# 3.net
KiCad netlist of a schematic drawn in Altium Designer
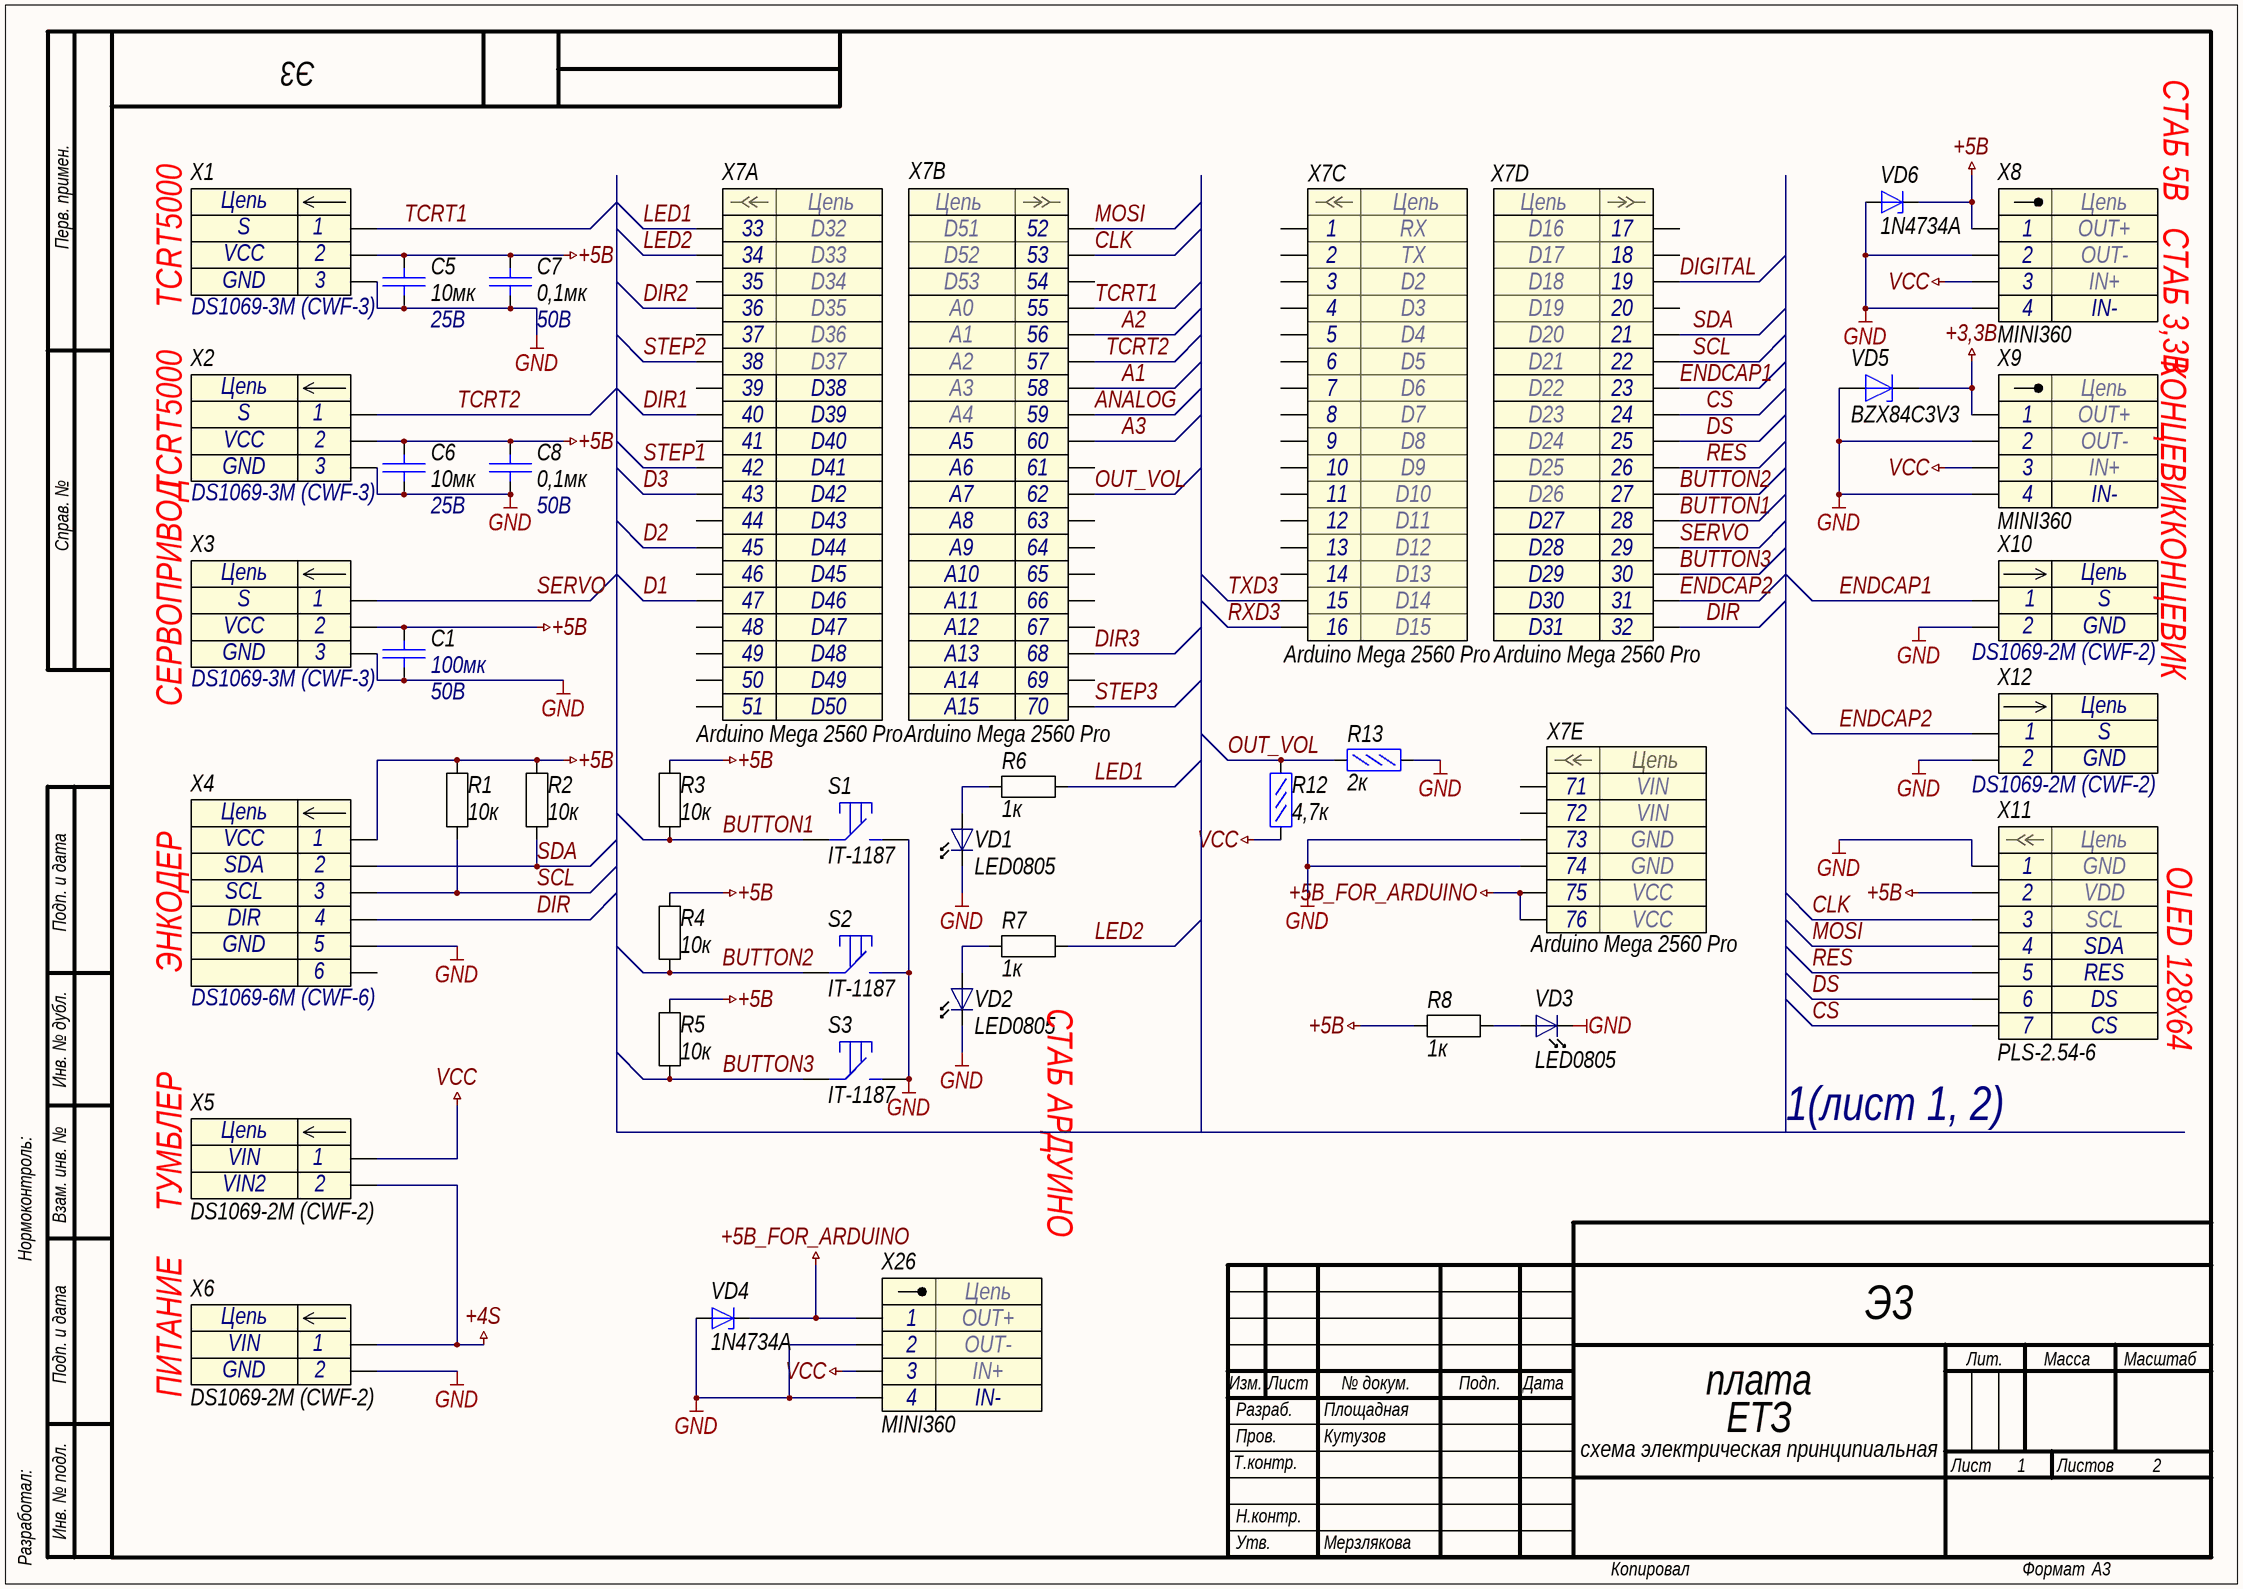
[diagram p0: Э3.SchDoc]

(export (version "E")
  (design (tool "Eeschema 10.0.6"))
  (components
    (comp (ref "C1")
      (value "100мк")
      (footprint "C1210")
      (description "Конденсатор кер. 100мк 50В")
      (fields (field (name "MANUFACTURER") "Yageo") (field (name "VOLTAGE") "50В"))
      (libsource (lib "capacitors") (part "CC0603JRNPO9BN220"))
    )
    (comp (ref "C5")
      (value "10мк")
      (footprint "C1206")
      (description "Конденсатор кер. 10мкФ 25В")
      (fields (field (name "MANUFACTURER") "Yageo") (field (name "VOLTAGE") "25В"))
      (libsource (lib "capacitors") (part "CC1206KKX7R8BB106"))
    )
    (comp (ref "C6")
      (value "10мк")
      (footprint "C1206")
      (description "Конденсатор кер. 10мкФ 25В")
      (fields (field (name "MANUFACTURER") "Yageo") (field (name "VOLTAGE") "25В"))
      (libsource (lib "capacitors") (part "CC1206KKX7R8BB106"))
    )
    (comp (ref "C7")
      (value "0,1мк")
      (footprint "C0603")
      (description "Конденсатор кер. 0,1мкФ 50В X7R")
      (fields (field (name "MANUFACTURER") "Murata") (field (name "VOLTAGE") "50В"))
      (libsource (lib "capacitors") (part "GRM188R71H104KA93D"))
    )
    (comp (ref "C8")
      (value "0,1мк")
      (footprint "C0603")
      (description "Конденсатор кер. 0,1мкФ 50В X7R")
      (fields (field (name "MANUFACTURER") "Murata") (field (name "VOLTAGE") "50В"))
      (libsource (lib "capacitors") (part "GRM188R71H104KA93D"))
    )
    (comp (ref "R1") (value "10к") (footprint "Resistor0805") (libsource (lib "") (part "RESISTOR_2")))
    (comp (ref "R2") (value "10к") (footprint "Resistor0805") (libsource (lib "") (part "RESISTOR_2")))
    (comp (ref "R3") (value "10к") (footprint "Resistor0805") (libsource (lib "") (part "RESISTOR_1")))
    (comp (ref "R4") (value "10к") (footprint "Resistor0805") (libsource (lib "") (part "RESISTOR_1")))
    (comp (ref "R5") (value "10к") (footprint "Resistor0805") (libsource (lib "") (part "RESISTOR_1")))
    (comp (ref "R6")
      (value "1к")
      (footprint "Resistor0805")
      (libsource (lib "LibraryPloshchadnaia") (part "RESISTOR"))
    )
    (comp (ref "R7")
      (value "1к")
      (footprint "Resistor0805")
      (libsource (lib "LibraryPloshchadnaia") (part "RESISTOR"))
    )
    (comp (ref "R8") (value "1к") (footprint "Resistor0805") (libsource (lib "") (part "RESISTOR_3")))
    (comp (ref "R12")
      (value "4,7к")
      (footprint "R0603")
      (description "Резистор 4,7кОм 0,063Вт 1%")
      (fields (field (name "MANUFACTURER") "YAGEO") (field (name "TOLERANCE") "1%"))
      (libsource (lib "resistors") (part "RC0603FR-074K7L"))
    )
    (comp (ref "R13")
      (value "2к")
      (footprint "R0603")
      (description "Резистор 2кОм 0,063Вт 1%")
      (fields (field (name "MANUFACTURER") "YAGEO") (field (name "TOLERANCE") "1%"))
      (libsource (lib "resistors") (part "RC0603FR-072KL"))
    )
    (comp (ref "S1")
      (value "IT-1187")
      (footprint "it-1187")
      (description "тактовая кнопка SMD")
      (libsource (lib "switches") (part "IT-1187"))
    )
    (comp (ref "S2")
      (value "IT-1187")
      (footprint "it-1187")
      (description "тактовая кнопка SMD")
      (libsource (lib "switches") (part "IT-1187"))
    )
    (comp (ref "S3")
      (value "IT-1187")
      (footprint "it-1187")
      (description "тактовая кнопка SMD")
      (libsource (lib "switches") (part "IT-1187"))
    )
    (comp (ref "VD1")
      (value "LED0805")
      (footprint "LED0805")
      (libsource (lib "LibraryPloshchadnaia") (part "LED0805"))
    )
    (comp (ref "VD2")
      (value "LED0805")
      (footprint "LED0805")
      (libsource (lib "LibraryPloshchadnaia") (part "LED0805"))
    )
    (comp (ref "VD3")
      (value "LED0805")
      (footprint "LED0805")
      (libsource (lib "LibraryPloshchadnaia") (part "LED0805"))
    )
    (comp (ref "VD4")
      (value "1N4734A")
      (footprint "DO-41")
      (description "Стабилитрон 5.6В, 5%, 1Вт, 1N4734A")
      (libsource (lib "diodes") (part "1N4734A"))
    )
    (comp (ref "VD5")
      (value "BZX84C3V3")
      (footprint "SOT23-3")
      (description "Стабилитрон 3,3В")
      (libsource (lib "diodes") (part "BZX84C3V3"))
    )
    (comp (ref "VD6")
      (value "1N4734A")
      (footprint "DO-41")
      (description "Стабилитрон 5.6В, 5%, 1Вт, 1N4734A")
      (libsource (lib "diodes") (part "1N4734A"))
    )
    (comp (ref "X1")
      (value "DS1069-3M (CWF-3)")
      (footprint "CWF-3")
      (description "Разъем - 3 конт. прямая вилка на плату")
      (fields (field (name "NAME") "DS1069-3M (CWF-3)"))
      (libsource (lib "headers") (part "CWF-3"))
    )
    (comp (ref "X2")
      (value "DS1069-3M (CWF-3)")
      (footprint "CWF-3")
      (description "Разъем - 3 конт. прямая вилка на плату")
      (fields (field (name "NAME") "DS1069-3M (CWF-3)"))
      (libsource (lib "headers") (part "CWF-3"))
    )
    (comp (ref "X3")
      (value "DS1069-3M (CWF-3)")
      (footprint "CWF-3")
      (description "Разъем - 3 конт. прямая вилка на плату")
      (fields (field (name "NAME") "DS1069-3M (CWF-3)"))
      (libsource (lib "headers") (part "CWF-3"))
    )
    (comp (ref "X4")
      (value "DS1069-6M (CWF-6)")
      (footprint "CWF-6")
      (description "Разъем - 6 конт. прямая вилка на плату")
      (fields (field (name "NAME") "DS1069-6M (CWF-6)"))
      (libsource (lib "headers") (part "CWF-6"))
    )
    (comp (ref "X5")
      (value "DS1069-2M (CWF-2)")
      (footprint "CWF-2")
      (description "Разъем - 2 конт. прямая вилка на плату")
      (libsource (lib "headers") (part "CWF-2"))
    )
    (comp (ref "X6")
      (value "DS1069-2M (CWF-2)")
      (footprint "CWF-2")
      (description "Разъем - 2 конт. прямая вилка на плату")
      (libsource (lib "headers") (part "CWF-2"))
    )
    (comp (ref "X7")
      (value "Arduino Mega 2560 Pro")
      (footprint "PBD38")
      (libsource (lib "LibraryPloshchadnaia") (part "Arduino Mega 2560 Pro"))
    )
    (comp (ref "X8")
      (value "MINI360")
      (footprint "mini360")
      (description "стаб 18 на 12 мм")
      (libsource (lib "LibraryPloshchadnaia") (part "mini360"))
    )
    (comp (ref "X9")
      (value "MINI360")
      (footprint "mini360")
      (description "стаб 18 на 12 мм")
      (libsource (lib "LibraryPloshchadnaia") (part "mini360"))
    )
    (comp (ref "X10")
      (value "DS1069-2M (CWF-2)")
      (footprint "CWF-2")
      (description "Разъем - 2 конт. прямая вилка на плату")
      (fields (field (name "NAME") "DS1069-2M (CWF-2)"))
      (libsource (lib "") (part "CWF-2_1"))
    )
    (comp (ref "X11")
      (value "PLS-2.54-6")
      (footprint "PBD8")
      (libsource (lib "LibraryPloshchadnaia") (part "PBD8"))
    )
    (comp (ref "X12")
      (value "DS1069-2M (CWF-2)")
      (footprint "CWF-2")
      (description "Разъем - 2 конт. прямая вилка на плату")
      (fields (field (name "NAME") "DS1069-2M (CWF-2)"))
      (libsource (lib "") (part "CWF-2_1"))
    )
    (comp (ref "X26")
      (value "MINI360")
      (footprint "mini360")
      (description "стаб 18 на 12 мм")
      (libsource (lib "LibraryPloshchadnaia") (part "mini360"))
    )
  )
  (nets
    (net (code "1") (name "+3,3В") (class "Default")
      (node (ref "VD5") (pin "3") (pinfunction "K_3") (pintype "passive"))
      (node (ref "X9") (pin "1") (pinfunction "1_1") (pintype "passive"))
    )
    (net (code "2") (name "+4S") (class "Default")
      (node (ref "X5") (pin "2") (pinfunction "2_2") (pintype "passive"))
      (node (ref "X6") (pin "1") (pinfunction "1_1") (pintype "passive"))
    )
    (net (code "3") (name "+5В") (class "Default")
      (node (ref "C1") (pin "2") (pinfunction "2_2") (pintype "passive"))
      (node (ref "C5") (pin "2") (pinfunction "2_2") (pintype "passive"))
      (node (ref "C6") (pin "2") (pinfunction "2_2") (pintype "passive"))
      (node (ref "C7") (pin "2") (pinfunction "2_2") (pintype "passive"))
      (node (ref "C8") (pin "2") (pinfunction "2_2") (pintype "passive"))
      (node (ref "R1") (pin "1") (pinfunction "1_1") (pintype "passive"))
      (node (ref "R2") (pin "1") (pinfunction "1_1") (pintype "passive"))
      (node (ref "R3") (pin "2") (pinfunction "2_2") (pintype "passive"))
      (node (ref "R4") (pin "2") (pinfunction "2_2") (pintype "passive"))
      (node (ref "R5") (pin "2") (pinfunction "2_2") (pintype "passive"))
      (node (ref "R8") (pin "1") (pinfunction "1_1") (pintype "passive"))
      (node (ref "VD6") (pin "2") (pinfunction "K_2") (pintype "passive"))
      (node (ref "X1") (pin "2") (pinfunction "2_2") (pintype "passive"))
      (node (ref "X11") (pin "2") (pinfunction "2_2") (pintype "passive"))
      (node (ref "X2") (pin "2") (pinfunction "2_2") (pintype "passive"))
      (node (ref "X3") (pin "2") (pinfunction "2_2") (pintype "passive"))
      (node (ref "X4") (pin "1") (pinfunction "1_1") (pintype "passive"))
      (node (ref "X8") (pin "1") (pinfunction "1_1") (pintype "passive"))
    )
    (net (code "4") (name "+5В_FOR_ARDUINO") (class "Default")
      (node (ref "VD4") (pin "2") (pinfunction "K_2") (pintype "passive"))
      (node (ref "X26") (pin "1") (pinfunction "1_1") (pintype "passive"))
      (node (ref "X7") (pin "75") (pinfunction "75_75") (pintype "passive"))
      (node (ref "X7") (pin "76") (pinfunction "76_76") (pintype "passive"))
    )
    (net (code "5") (name "/A1") (class "Default")
      (node (ref "X7") (pin "58") (pinfunction "58_58") (pintype "passive"))
    )
    (net (code "6") (name "/A2") (class "Default")
      (node (ref "X7") (pin "56") (pinfunction "56_56") (pintype "passive"))
    )
    (net (code "7") (name "/A3") (class "Default")
      (node (ref "X7") (pin "60") (pinfunction "60_60") (pintype "passive"))
    )
    (net (code "8") (name "/ANALOG") (class "Default")
      (node (ref "X7") (pin "59") (pinfunction "59_59") (pintype "passive"))
    )
    (net (code "9") (name "/BUTTON1") (class "Default")
      (node (ref "R3") (pin "1") (pinfunction "1_1") (pintype "passive"))
      (node (ref "S1") (pin "1") (pinfunction "1_1") (pintype "passive"))
      (node (ref "X7") (pin "28") (pinfunction "28_28") (pintype "passive"))
    )
    (net (code "10") (name "/BUTTON2") (class "Default")
      (node (ref "R4") (pin "1") (pinfunction "1_1") (pintype "passive"))
      (node (ref "S2") (pin "1") (pinfunction "1_1") (pintype "passive"))
      (node (ref "X7") (pin "27") (pinfunction "27_27") (pintype "passive"))
    )
    (net (code "11") (name "/BUTTON3") (class "Default")
      (node (ref "R5") (pin "1") (pinfunction "1_1") (pintype "passive"))
      (node (ref "S3") (pin "1") (pinfunction "1_1") (pintype "passive"))
      (node (ref "X7") (pin "30") (pinfunction "30_30") (pintype "passive"))
    )
    (net (code "12") (name "/CLK") (class "Default")
      (node (ref "X11") (pin "3") (pinfunction "3_3") (pintype "passive"))
      (node (ref "X7") (pin "53") (pinfunction "53_53") (pintype "passive"))
    )
    (net (code "13") (name "/CS") (class "Default")
      (node (ref "X11") (pin "7") (pinfunction "7_7") (pintype "passive"))
      (node (ref "X7") (pin "24") (pinfunction "24_24") (pintype "passive"))
    )
    (net (code "14") (name "/D1") (class "Default")
      (node (ref "X7") (pin "47") (pinfunction "47_47") (pintype "passive"))
    )
    (net (code "15") (name "/D2") (class "Default")
      (node (ref "X7") (pin "45") (pinfunction "45_45") (pintype "passive"))
    )
    (net (code "16") (name "/D3") (class "Default")
      (node (ref "X7") (pin "43") (pinfunction "43_43") (pintype "passive"))
    )
    (net (code "17") (name "/DIGITAL") (class "Default")
      (node (ref "X7") (pin "19") (pinfunction "19_19") (pintype "passive"))
    )
    (net (code "18") (name "/DIR") (class "Default")
      (node (ref "X4") (pin "4") (pinfunction "4_4") (pintype "passive"))
      (node (ref "X7") (pin "32") (pinfunction "32_32") (pintype "passive"))
    )
    (net (code "19") (name "/DIR1") (class "Default")
      (node (ref "X7") (pin "40") (pinfunction "40_40") (pintype "passive"))
    )
    (net (code "20") (name "/DIR2") (class "Default")
      (node (ref "X7") (pin "36") (pinfunction "36_36") (pintype "passive"))
    )
    (net (code "21") (name "/DIR3") (class "Default")
      (node (ref "X7") (pin "68") (pinfunction "68_68") (pintype "passive"))
    )
    (net (code "22") (name "/DS") (class "Default")
      (node (ref "X11") (pin "6") (pinfunction "6_6") (pintype "passive"))
      (node (ref "X7") (pin "25") (pinfunction "25_25") (pintype "passive"))
    )
    (net (code "23") (name "/ENDCAP1") (class "Default")
      (node (ref "X10") (pin "1") (pinfunction "1_1") (pintype "passive"))
      (node (ref "X7") (pin "23") (pinfunction "23_23") (pintype "passive"))
    )
    (net (code "24") (name "/ENDCAP2") (class "Default")
      (node (ref "X12") (pin "1") (pinfunction "1_1") (pintype "passive"))
      (node (ref "X7") (pin "31") (pinfunction "31_31") (pintype "passive"))
    )
    (net (code "25") (name "/LED1") (class "Default")
      (node (ref "R6") (pin "1") (pinfunction "1_1") (pintype "passive"))
      (node (ref "X7") (pin "33") (pinfunction "33_33") (pintype "passive"))
    )
    (net (code "26") (name "/LED2") (class "Default")
      (node (ref "R7") (pin "1") (pinfunction "1_1") (pintype "passive"))
      (node (ref "X7") (pin "34") (pinfunction "34_34") (pintype "passive"))
    )
    (net (code "27") (name "/MOSI") (class "Default")
      (node (ref "X11") (pin "4") (pinfunction "4_4") (pintype "passive"))
      (node (ref "X7") (pin "52") (pinfunction "52_52") (pintype "passive"))
    )
    (net (code "28") (name "/OUT_VOL") (class "Default")
      (node (ref "R12") (pin "2") (pinfunction "2_2") (pintype "passive"))
      (node (ref "R13") (pin "1") (pinfunction "1_1") (pintype "passive"))
      (node (ref "X7") (pin "62") (pinfunction "62_62") (pintype "passive"))
    )
    (net (code "29") (name "/RES") (class "Default")
      (node (ref "X11") (pin "5") (pinfunction "5_5") (pintype "passive"))
      (node (ref "X7") (pin "26") (pinfunction "26_26") (pintype "passive"))
    )
    (net (code "30") (name "/RXD3") (class "Default")
      (node (ref "X7") (pin "16") (pinfunction "16_16") (pintype "passive"))
    )
    (net (code "31") (name "/SCL") (class "Default")
      (node (ref "R1") (pin "2") (pinfunction "2_2") (pintype "passive"))
      (node (ref "X4") (pin "3") (pinfunction "3_3") (pintype "passive"))
      (node (ref "X7") (pin "22") (pinfunction "22_22") (pintype "passive"))
    )
    (net (code "32") (name "/SDA") (class "Default")
      (node (ref "R2") (pin "2") (pinfunction "2_2") (pintype "passive"))
      (node (ref "X4") (pin "2") (pinfunction "2_2") (pintype "passive"))
      (node (ref "X7") (pin "21") (pinfunction "21_21") (pintype "passive"))
    )
    (net (code "33") (name "/SERVO") (class "Default")
      (node (ref "X3") (pin "1") (pinfunction "1_1") (pintype "passive"))
      (node (ref "X7") (pin "29") (pinfunction "29_29") (pintype "passive"))
    )
    (net (code "34") (name "/STEP1") (class "Default")
      (node (ref "X7") (pin "42") (pinfunction "42_42") (pintype "passive"))
    )
    (net (code "35") (name "/STEP2") (class "Default")
      (node (ref "X7") (pin "38") (pinfunction "38_38") (pintype "passive"))
    )
    (net (code "36") (name "/STEP3") (class "Default")
      (node (ref "X7") (pin "70") (pinfunction "70_70") (pintype "passive"))
    )
    (net (code "37") (name "/TCRT1") (class "Default")
      (node (ref "X1") (pin "1") (pinfunction "1_1") (pintype "passive"))
      (node (ref "X7") (pin "55") (pinfunction "55_55") (pintype "passive"))
    )
    (net (code "38") (name "/TCRT2") (class "Default")
      (node (ref "X2") (pin "1") (pinfunction "1_1") (pintype "passive"))
      (node (ref "X7") (pin "57") (pinfunction "57_57") (pintype "passive"))
    )
    (net (code "39") (name "/TXD3") (class "Default")
      (node (ref "X7") (pin "15") (pinfunction "15_15") (pintype "passive"))
    )
    (net (code "40") (name "GND") (class "Default")
      (node (ref "C1") (pin "1") (pinfunction "1_1") (pintype "passive"))
      (node (ref "C5") (pin "1") (pinfunction "1_1") (pintype "passive"))
      (node (ref "C6") (pin "1") (pinfunction "1_1") (pintype "passive"))
      (node (ref "C7") (pin "1") (pinfunction "1_1") (pintype "passive"))
      (node (ref "C8") (pin "1") (pinfunction "1_1") (pintype "passive"))
      (node (ref "R13") (pin "2") (pinfunction "2_2") (pintype "passive"))
      (node (ref "S1") (pin "2") (pinfunction "2_2") (pintype "passive"))
      (node (ref "S2") (pin "2") (pinfunction "2_2") (pintype "passive"))
      (node (ref "S3") (pin "2") (pinfunction "2_2") (pintype "passive"))
      (node (ref "VD1") (pin "1") (pinfunction "1_1") (pintype "passive"))
      (node (ref "VD2") (pin "1") (pinfunction "1_1") (pintype "passive"))
      (node (ref "VD3") (pin "1") (pinfunction "1_1") (pintype "passive"))
      (node (ref "VD4") (pin "1") (pinfunction "A_1") (pintype "passive"))
      (node (ref "VD5") (pin "1") (pinfunction "A_1") (pintype "passive"))
      (node (ref "VD6") (pin "1") (pinfunction "A_1") (pintype "passive"))
      (node (ref "X1") (pin "3") (pinfunction "3_3") (pintype "passive"))
      (node (ref "X10") (pin "2") (pinfunction "2_2") (pintype "passive"))
      (node (ref "X11") (pin "1") (pinfunction "1_1") (pintype "passive"))
      (node (ref "X12") (pin "2") (pinfunction "2_2") (pintype "passive"))
      (node (ref "X2") (pin "3") (pinfunction "3_3") (pintype "passive"))
      (node (ref "X26") (pin "2") (pinfunction "2_2") (pintype "passive"))
      (node (ref "X26") (pin "4") (pinfunction "4_4") (pintype "passive"))
      (node (ref "X3") (pin "3") (pinfunction "3_3") (pintype "passive"))
      (node (ref "X4") (pin "5") (pinfunction "5_5") (pintype "passive"))
      (node (ref "X6") (pin "2") (pinfunction "2_2") (pintype "passive"))
      (node (ref "X7") (pin "73") (pinfunction "73_73") (pintype "passive"))
      (node (ref "X7") (pin "74") (pinfunction "74_74") (pintype "passive"))
      (node (ref "X8") (pin "2") (pinfunction "2_2") (pintype "passive"))
      (node (ref "X8") (pin "4") (pinfunction "4_4") (pintype "passive"))
      (node (ref "X9") (pin "2") (pinfunction "2_2") (pintype "passive"))
      (node (ref "X9") (pin "4") (pinfunction "4_4") (pintype "passive"))
    )
    (net (code "41") (name "Net-(R6-Pad2)") (class "Default")
      (node (ref "R6") (pin "2") (pinfunction "2_2") (pintype "passive"))
      (node (ref "VD1") (pin "2") (pinfunction "2_2") (pintype "passive"))
    )
    (net (code "42") (name "Net-(R7-Pad2)") (class "Default")
      (node (ref "R7") (pin "2") (pinfunction "2_2") (pintype "passive"))
      (node (ref "VD2") (pin "2") (pinfunction "2_2") (pintype "passive"))
    )
    (net (code "43") (name "Net-(R8-Pad2)") (class "Default")
      (node (ref "R8") (pin "2") (pinfunction "2_2") (pintype "passive"))
      (node (ref "VD3") (pin "2") (pinfunction "2_2") (pintype "passive"))
    )
    (net (code "44") (name "VCC") (class "Default")
      (node (ref "R12") (pin "1") (pinfunction "1_1") (pintype "passive"))
      (node (ref "X26") (pin "3") (pinfunction "3_3") (pintype "passive"))
      (node (ref "X5") (pin "1") (pinfunction "1_1") (pintype "passive"))
      (node (ref "X8") (pin "3") (pinfunction "3_3") (pintype "passive"))
      (node (ref "X9") (pin "3") (pinfunction "3_3") (pintype "passive"))
    )
    (net (code "45") (name "unconnected-(X4-Pad6)") (class "Default")
      (node (ref "X4") (pin "6") (pinfunction "6_6") (pintype "passive"))
    )
    (net (code "46") (name "unconnected-(X7-Pad1)") (class "Default")
      (node (ref "X7") (pin "1") (pinfunction "1_1") (pintype "passive"))
    )
    (net (code "47") (name "unconnected-(X7-Pad2)") (class "Default")
      (node (ref "X7") (pin "2") (pinfunction "2_2") (pintype "passive"))
    )
    (net (code "48") (name "unconnected-(X7-Pad3)") (class "Default")
      (node (ref "X7") (pin "3") (pinfunction "3_3") (pintype "passive"))
    )
    (net (code "49") (name "unconnected-(X7-Pad4)") (class "Default")
      (node (ref "X7") (pin "4") (pinfunction "4_4") (pintype "passive"))
    )
    (net (code "50") (name "unconnected-(X7-Pad5)") (class "Default")
      (node (ref "X7") (pin "5") (pinfunction "5_5") (pintype "passive"))
    )
    (net (code "51") (name "unconnected-(X7-Pad6)") (class "Default")
      (node (ref "X7") (pin "6") (pinfunction "6_6") (pintype "passive"))
    )
    (net (code "52") (name "unconnected-(X7-Pad7)") (class "Default")
      (node (ref "X7") (pin "7") (pinfunction "7_7") (pintype "passive"))
    )
    (net (code "53") (name "unconnected-(X7-Pad8)") (class "Default")
      (node (ref "X7") (pin "8") (pinfunction "8_8") (pintype "passive"))
    )
    (net (code "54") (name "unconnected-(X7-Pad9)") (class "Default")
      (node (ref "X7") (pin "9") (pinfunction "9_9") (pintype "passive"))
    )
    (net (code "55") (name "unconnected-(X7-Pad10)") (class "Default")
      (node (ref "X7") (pin "10") (pinfunction "10_10") (pintype "passive"))
    )
    (net (code "56") (name "unconnected-(X7-Pad11)") (class "Default")
      (node (ref "X7") (pin "11") (pinfunction "11_11") (pintype "passive"))
    )
    (net (code "57") (name "unconnected-(X7-Pad12)") (class "Default")
      (node (ref "X7") (pin "12") (pinfunction "12_12") (pintype "passive"))
    )
    (net (code "58") (name "unconnected-(X7-Pad13)") (class "Default")
      (node (ref "X7") (pin "13") (pinfunction "13_13") (pintype "passive"))
    )
    (net (code "59") (name "unconnected-(X7-Pad14)") (class "Default")
      (node (ref "X7") (pin "14") (pinfunction "14_14") (pintype "passive"))
    )
    (net (code "60") (name "unconnected-(X7-Pad17)") (class "Default")
      (node (ref "X7") (pin "17") (pinfunction "17_17") (pintype "passive"))
    )
    (net (code "61") (name "unconnected-(X7-Pad18)") (class "Default")
      (node (ref "X7") (pin "18") (pinfunction "18_18") (pintype "passive"))
    )
    (net (code "62") (name "unconnected-(X7-Pad20)") (class "Default")
      (node (ref "X7") (pin "20") (pinfunction "20_20") (pintype "passive"))
    )
    (net (code "63") (name "unconnected-(X7-Pad35)") (class "Default")
      (node (ref "X7") (pin "35") (pinfunction "35_35") (pintype "passive"))
    )
    (net (code "64") (name "unconnected-(X7-Pad37)") (class "Default")
      (node (ref "X7") (pin "37") (pinfunction "37_37") (pintype "passive"))
    )
    (net (code "65") (name "unconnected-(X7-Pad39)") (class "Default")
      (node (ref "X7") (pin "39") (pinfunction "39_39") (pintype "passive"))
    )
    (net (code "66") (name "unconnected-(X7-Pad41)") (class "Default")
      (node (ref "X7") (pin "41") (pinfunction "41_41") (pintype "passive"))
    )
    (net (code "67") (name "unconnected-(X7-Pad44)") (class "Default")
      (node (ref "X7") (pin "44") (pinfunction "44_44") (pintype "passive"))
    )
    (net (code "68") (name "unconnected-(X7-Pad46)") (class "Default")
      (node (ref "X7") (pin "46") (pinfunction "46_46") (pintype "passive"))
    )
    (net (code "69") (name "unconnected-(X7-Pad48)") (class "Default")
      (node (ref "X7") (pin "48") (pinfunction "48_48") (pintype "passive"))
    )
    (net (code "70") (name "unconnected-(X7-Pad49)") (class "Default")
      (node (ref "X7") (pin "49") (pinfunction "49_49") (pintype "passive"))
    )
    (net (code "71") (name "unconnected-(X7-Pad50)") (class "Default")
      (node (ref "X7") (pin "50") (pinfunction "50_50") (pintype "passive"))
    )
    (net (code "72") (name "unconnected-(X7-Pad51)") (class "Default")
      (node (ref "X7") (pin "51") (pinfunction "51_51") (pintype "passive"))
    )
    (net (code "73") (name "unconnected-(X7-Pad54)") (class "Default")
      (node (ref "X7") (pin "54") (pinfunction "54_54") (pintype "passive"))
    )
    (net (code "74") (name "unconnected-(X7-Pad61)") (class "Default")
      (node (ref "X7") (pin "61") (pinfunction "61_61") (pintype "passive"))
    )
    (net (code "75") (name "unconnected-(X7-Pad63)") (class "Default")
      (node (ref "X7") (pin "63") (pinfunction "63_63") (pintype "passive"))
    )
    (net (code "76") (name "unconnected-(X7-Pad64)") (class "Default")
      (node (ref "X7") (pin "64") (pinfunction "64_64") (pintype "passive"))
    )
    (net (code "77") (name "unconnected-(X7-Pad65)") (class "Default")
      (node (ref "X7") (pin "65") (pinfunction "65_65") (pintype "passive"))
    )
    (net (code "78") (name "unconnected-(X7-Pad66)") (class "Default")
      (node (ref "X7") (pin "66") (pinfunction "66_66") (pintype "passive"))
    )
    (net (code "79") (name "unconnected-(X7-Pad67)") (class "Default")
      (node (ref "X7") (pin "67") (pinfunction "67_67") (pintype "passive"))
    )
    (net (code "80") (name "unconnected-(X7-Pad69)") (class "Default")
      (node (ref "X7") (pin "69") (pinfunction "69_69") (pintype "passive"))
    )
    (net (code "81") (name "unconnected-(X7-Pad71)") (class "Default")
      (node (ref "X7") (pin "71") (pinfunction "71_71") (pintype "passive"))
    )
    (net (code "82") (name "unconnected-(X7-Pad72)") (class "Default")
      (node (ref "X7") (pin "72") (pinfunction "72_72") (pintype "passive"))
    )
  )
)
